# WS2812.net
KiCad netlist of a schematic drawn in Altium Designer
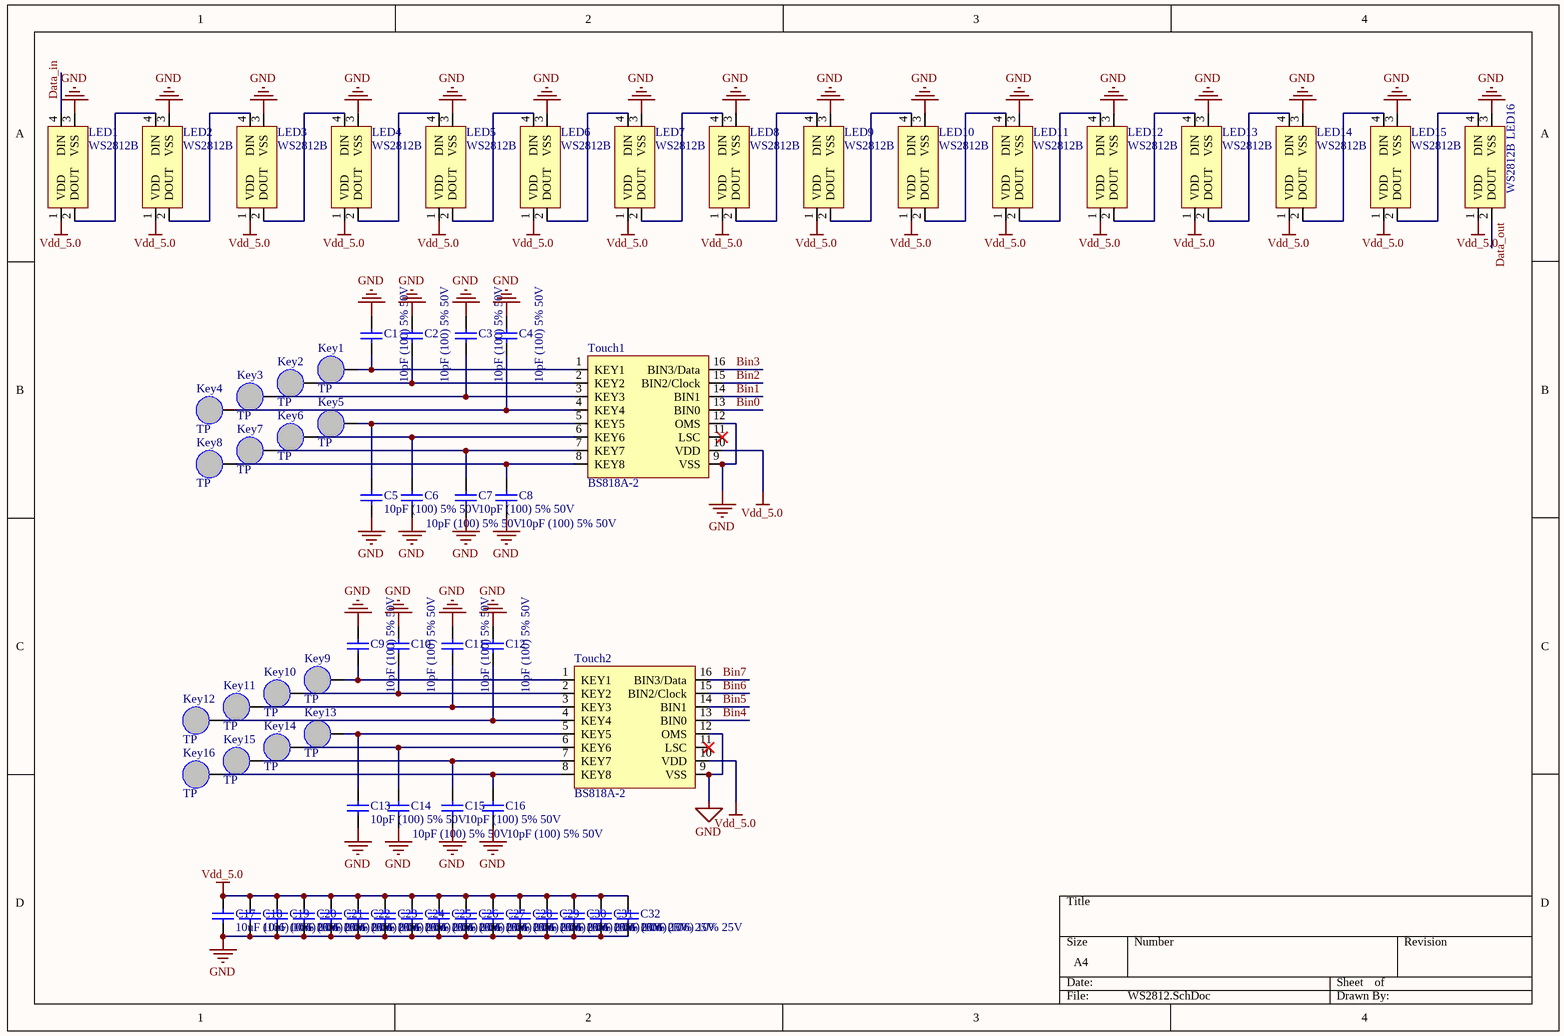
[diagram p0: WS2812.SchDoc]

(export (version "E")
  (design (tool "Eeschema 10.0.6"))
  (components
    (comp (ref "C1")
      (value "10pF (100) 5% 50V")
      (footprint "0603_C")
      (description "贴片电容")
      (libsource (lib "Miscellaneous Devices LC") (part "0603 10pF (100) 5% 50V"))
    )
    (comp (ref "C2")
      (value "10pF (100) 5% 50V")
      (footprint "0603_C")
      (description "贴片电容")
      (libsource (lib "Miscellaneous Devices LC") (part "0603 10pF (100) 5% 50V"))
    )
    (comp (ref "C3")
      (value "10pF (100) 5% 50V")
      (footprint "0603_C")
      (description "贴片电容")
      (libsource (lib "Miscellaneous Devices LC") (part "0603 10pF (100) 5% 50V"))
    )
    (comp (ref "C4")
      (value "10pF (100) 5% 50V")
      (footprint "0603_C")
      (description "贴片电容")
      (libsource (lib "Miscellaneous Devices LC") (part "0603 10pF (100) 5% 50V"))
    )
    (comp (ref "C5")
      (value "10pF (100) 5% 50V")
      (footprint "0603_C")
      (description "贴片电容")
      (libsource (lib "Miscellaneous Devices LC") (part "0603 10pF (100) 5% 50V"))
    )
    (comp (ref "C6")
      (value "10pF (100) 5% 50V")
      (footprint "0603_C")
      (description "贴片电容")
      (libsource (lib "Miscellaneous Devices LC") (part "0603 10pF (100) 5% 50V"))
    )
    (comp (ref "C7")
      (value "10pF (100) 5% 50V")
      (footprint "0603_C")
      (description "贴片电容")
      (libsource (lib "Miscellaneous Devices LC") (part "0603 10pF (100) 5% 50V"))
    )
    (comp (ref "C8")
      (value "10pF (100) 5% 50V")
      (footprint "0603_C")
      (description "贴片电容")
      (libsource (lib "Miscellaneous Devices LC") (part "0603 10pF (100) 5% 50V"))
    )
    (comp (ref "C9")
      (value "10pF (100) 5% 50V")
      (footprint "0603_C")
      (description "贴片电容")
      (libsource (lib "Miscellaneous Devices LC") (part "0603 10pF (100) 5% 50V"))
    )
    (comp (ref "C10")
      (value "10pF (100) 5% 50V")
      (footprint "0603_C")
      (description "贴片电容")
      (libsource (lib "Miscellaneous Devices LC") (part "0603 10pF (100) 5% 50V"))
    )
    (comp (ref "C11")
      (value "10pF (100) 5% 50V")
      (footprint "0603_C")
      (description "贴片电容")
      (libsource (lib "Miscellaneous Devices LC") (part "0603 10pF (100) 5% 50V"))
    )
    (comp (ref "C12")
      (value "10pF (100) 5% 50V")
      (footprint "0603_C")
      (description "贴片电容")
      (libsource (lib "Miscellaneous Devices LC") (part "0603 10pF (100) 5% 50V"))
    )
    (comp (ref "C13")
      (value "10pF (100) 5% 50V")
      (footprint "0603_C")
      (description "贴片电容")
      (libsource (lib "Miscellaneous Devices LC") (part "0603 10pF (100) 5% 50V"))
    )
    (comp (ref "C14")
      (value "10pF (100) 5% 50V")
      (footprint "0603_C")
      (description "贴片电容")
      (libsource (lib "Miscellaneous Devices LC") (part "0603 10pF (100) 5% 50V"))
    )
    (comp (ref "C15")
      (value "10pF (100) 5% 50V")
      (footprint "0603_C")
      (description "贴片电容")
      (libsource (lib "Miscellaneous Devices LC") (part "0603 10pF (100) 5% 50V"))
    )
    (comp (ref "C16")
      (value "10pF (100) 5% 50V")
      (footprint "0603_C")
      (description "贴片电容")
      (libsource (lib "Miscellaneous Devices LC") (part "0603 10pF (100) 5% 50V"))
    )
    (comp (ref "C17")
      (value "10uF (106) 10% 25V")
      (footprint "0805_C")
      (description "贴片电容")
      (libsource (lib "Miscellaneous Devices LC") (part "0805 10uF (106) 10% 25V"))
    )
    (comp (ref "C18")
      (value "10uF (106) 10% 25V")
      (footprint "0805_C")
      (description "贴片电容")
      (libsource (lib "Miscellaneous Devices LC") (part "0805 10uF (106) 10% 25V"))
    )
    (comp (ref "C19")
      (value "10uF (106) 10% 25V")
      (footprint "0805_C")
      (description "贴片电容")
      (libsource (lib "Miscellaneous Devices LC") (part "0805 10uF (106) 10% 25V"))
    )
    (comp (ref "C20")
      (value "10uF (106) 10% 25V")
      (footprint "0805_C")
      (description "贴片电容")
      (libsource (lib "Miscellaneous Devices LC") (part "0805 10uF (106) 10% 25V"))
    )
    (comp (ref "C21")
      (value "10uF (106) 10% 25V")
      (footprint "0805_C")
      (description "贴片电容")
      (libsource (lib "Miscellaneous Devices LC") (part "0805 10uF (106) 10% 25V"))
    )
    (comp (ref "C22")
      (value "10uF (106) 10% 25V")
      (footprint "0805_C")
      (description "贴片电容")
      (libsource (lib "Miscellaneous Devices LC") (part "0805 10uF (106) 10% 25V"))
    )
    (comp (ref "C23")
      (value "10uF (106) 10% 25V")
      (footprint "0805_C")
      (description "贴片电容")
      (libsource (lib "Miscellaneous Devices LC") (part "0805 10uF (106) 10% 25V"))
    )
    (comp (ref "C24")
      (value "10uF (106) 10% 25V")
      (footprint "0805_C")
      (description "贴片电容")
      (libsource (lib "Miscellaneous Devices LC") (part "0805 10uF (106) 10% 25V"))
    )
    (comp (ref "C25")
      (value "10uF (106) 10% 25V")
      (footprint "0805_C")
      (description "贴片电容")
      (libsource (lib "Miscellaneous Devices LC") (part "0805 10uF (106) 10% 25V"))
    )
    (comp (ref "C26")
      (value "10uF (106) 10% 25V")
      (footprint "0805_C")
      (description "贴片电容")
      (libsource (lib "Miscellaneous Devices LC") (part "0805 10uF (106) 10% 25V"))
    )
    (comp (ref "C27")
      (value "10uF (106) 10% 25V")
      (footprint "0805_C")
      (description "贴片电容")
      (libsource (lib "Miscellaneous Devices LC") (part "0805 10uF (106) 10% 25V"))
    )
    (comp (ref "C28")
      (value "10uF (106) 10% 25V")
      (footprint "0805_C")
      (description "贴片电容")
      (libsource (lib "Miscellaneous Devices LC") (part "0805 10uF (106) 10% 25V"))
    )
    (comp (ref "C29")
      (value "10uF (106) 10% 25V")
      (footprint "0805_C")
      (description "贴片电容")
      (libsource (lib "Miscellaneous Devices LC") (part "0805 10uF (106) 10% 25V"))
    )
    (comp (ref "C30")
      (value "10uF (106) 10% 25V")
      (footprint "0805_C")
      (description "贴片电容")
      (libsource (lib "Miscellaneous Devices LC") (part "0805 10uF (106) 10% 25V"))
    )
    (comp (ref "C31")
      (value "10uF (106) 10% 25V")
      (footprint "0805_C")
      (description "贴片电容")
      (libsource (lib "Miscellaneous Devices LC") (part "0805 10uF (106) 10% 25V"))
    )
    (comp (ref "C32")
      (value "10uF (106) 10% 25V")
      (footprint "0805_C")
      (description "贴片电容")
      (libsource (lib "Miscellaneous Devices LC") (part "0805 10uF (106) 10% 25V"))
    )
    (comp (ref "Key1") (value "TP") (footprint "Spring_touch") (libsource (lib "mylib") (part "TP")))
    (comp (ref "Key2") (value "TP") (footprint "Spring_touch") (libsource (lib "mylib") (part "TP")))
    (comp (ref "Key3") (value "TP") (footprint "Spring_touch") (libsource (lib "mylib") (part "TP")))
    (comp (ref "Key4") (value "TP") (footprint "Spring_touch") (libsource (lib "mylib") (part "TP")))
    (comp (ref "Key5") (value "TP") (footprint "Spring_touch") (libsource (lib "mylib") (part "TP")))
    (comp (ref "Key6") (value "TP") (footprint "Spring_touch") (libsource (lib "mylib") (part "TP")))
    (comp (ref "Key7") (value "TP") (footprint "Spring_touch") (libsource (lib "mylib") (part "TP")))
    (comp (ref "Key8") (value "TP") (footprint "Spring_touch") (libsource (lib "mylib") (part "TP")))
    (comp (ref "Key9") (value "TP") (footprint "Spring_touch") (libsource (lib "mylib") (part "TP")))
    (comp (ref "Key10") (value "TP") (footprint "Spring_touch") (libsource (lib "mylib") (part "TP")))
    (comp (ref "Key11") (value "TP") (footprint "Spring_touch") (libsource (lib "mylib") (part "TP")))
    (comp (ref "Key12") (value "TP") (footprint "Spring_touch") (libsource (lib "mylib") (part "TP")))
    (comp (ref "Key13") (value "TP") (footprint "Spring_touch") (libsource (lib "mylib") (part "TP")))
    (comp (ref "Key14") (value "TP") (footprint "Spring_touch") (libsource (lib "mylib") (part "TP")))
    (comp (ref "Key15") (value "TP") (footprint "Spring_touch") (libsource (lib "mylib") (part "TP")))
    (comp (ref "Key16") (value "TP") (footprint "Spring_touch") (libsource (lib "mylib") (part "TP")))
    (comp (ref "LED1") (value "WS2812B") (footprint "WS2812") (libsource (lib "mylib") (part "WS2812B")))
    (comp (ref "LED2") (value "WS2812B") (footprint "WS2812") (libsource (lib "mylib") (part "WS2812B")))
    (comp (ref "LED3") (value "WS2812B") (footprint "WS2812") (libsource (lib "mylib") (part "WS2812B")))
    (comp (ref "LED4") (value "WS2812B") (footprint "WS2812") (libsource (lib "mylib") (part "WS2812B")))
    (comp (ref "LED5") (value "WS2812B") (footprint "WS2812") (libsource (lib "mylib") (part "WS2812B")))
    (comp (ref "LED6") (value "WS2812B") (footprint "WS2812") (libsource (lib "mylib") (part "WS2812B")))
    (comp (ref "LED7") (value "WS2812B") (footprint "WS2812") (libsource (lib "mylib") (part "WS2812B")))
    (comp (ref "LED8") (value "WS2812B") (footprint "WS2812") (libsource (lib "mylib") (part "WS2812B")))
    (comp (ref "LED9") (value "WS2812B") (footprint "WS2812") (libsource (lib "mylib") (part "WS2812B")))
    (comp (ref "LED10") (value "WS2812B") (footprint "WS2812") (libsource (lib "mylib") (part "WS2812B")))
    (comp (ref "LED11") (value "WS2812B") (footprint "WS2812") (libsource (lib "mylib") (part "WS2812B")))
    (comp (ref "LED12") (value "WS2812B") (footprint "WS2812") (libsource (lib "mylib") (part "WS2812B")))
    (comp (ref "LED13") (value "WS2812B") (footprint "WS2812") (libsource (lib "mylib") (part "WS2812B")))
    (comp (ref "LED14") (value "WS2812B") (footprint "WS2812") (libsource (lib "mylib") (part "WS2812B")))
    (comp (ref "LED15") (value "WS2812B") (footprint "WS2812") (libsource (lib "mylib") (part "WS2812B")))
    (comp (ref "LED16") (value "WS2812B") (footprint "WS2812") (libsource (lib "mylib") (part "WS2812B")))
    (comp (ref "Touch1") (value "BS818A-2") (footprint "SO-16_N") (libsource (lib "mylib") (part "BS818A-2")))
    (comp (ref "Touch2") (value "BS818A-2") (footprint "SO-16_N") (libsource (lib "mylib") (part "BS818A-2")))
  )
  (nets
    (net (code "1") (name "/Bin0") (class "Default")
      (node (ref "Touch1") (pin "13") (pinfunction "BIN0_13") (pintype "passive"))
    )
    (net (code "2") (name "/Bin1") (class "Default")
      (node (ref "Touch1") (pin "14") (pinfunction "BIN1_14") (pintype "passive"))
    )
    (net (code "3") (name "/Bin2") (class "Default")
      (node (ref "Touch1") (pin "15") (pinfunction "BIN2/Clock_15") (pintype "passive"))
    )
    (net (code "4") (name "/Bin3") (class "Default")
      (node (ref "Touch1") (pin "16") (pinfunction "BIN3/Data_16") (pintype "passive"))
    )
    (net (code "5") (name "/Bin4") (class "Default")
      (node (ref "Touch2") (pin "13") (pinfunction "BIN0_13") (pintype "passive"))
    )
    (net (code "6") (name "/Bin5") (class "Default")
      (node (ref "Touch2") (pin "14") (pinfunction "BIN1_14") (pintype "passive"))
    )
    (net (code "7") (name "/Bin6") (class "Default")
      (node (ref "Touch2") (pin "15") (pinfunction "BIN2/Clock_15") (pintype "passive"))
    )
    (net (code "8") (name "/Bin7") (class "Default")
      (node (ref "Touch2") (pin "16") (pinfunction "BIN3/Data_16") (pintype "passive"))
    )
    (net (code "9") (name "/Data_in") (class "Default")
      (node (ref "LED1") (pin "4") (pinfunction "DIN_4") (pintype "passive"))
    )
    (net (code "10") (name "/Data_out") (class "Default")
      (node (ref "LED16") (pin "2") (pinfunction "DOUT_2") (pintype "passive"))
    )
    (net (code "11") (name "GND") (class "Default")
      (node (ref "C1") (pin "2") (pinfunction "2_2") (pintype "passive"))
      (node (ref "C10") (pin "2") (pinfunction "2_2") (pintype "passive"))
      (node (ref "C11") (pin "2") (pinfunction "2_2") (pintype "passive"))
      (node (ref "C12") (pin "2") (pinfunction "2_2") (pintype "passive"))
      (node (ref "C13") (pin "2") (pinfunction "2_2") (pintype "passive"))
      (node (ref "C14") (pin "2") (pinfunction "2_2") (pintype "passive"))
      (node (ref "C15") (pin "2") (pinfunction "2_2") (pintype "passive"))
      (node (ref "C16") (pin "2") (pinfunction "2_2") (pintype "passive"))
      (node (ref "C17") (pin "1") (pinfunction "1_1") (pintype "passive"))
      (node (ref "C18") (pin "1") (pinfunction "1_1") (pintype "passive"))
      (node (ref "C19") (pin "1") (pinfunction "1_1") (pintype "passive"))
      (node (ref "C2") (pin "2") (pinfunction "2_2") (pintype "passive"))
      (node (ref "C20") (pin "1") (pinfunction "1_1") (pintype "passive"))
      (node (ref "C21") (pin "1") (pinfunction "1_1") (pintype "passive"))
      (node (ref "C22") (pin "1") (pinfunction "1_1") (pintype "passive"))
      (node (ref "C23") (pin "1") (pinfunction "1_1") (pintype "passive"))
      (node (ref "C24") (pin "1") (pinfunction "1_1") (pintype "passive"))
      (node (ref "C25") (pin "1") (pinfunction "1_1") (pintype "passive"))
      (node (ref "C26") (pin "1") (pinfunction "1_1") (pintype "passive"))
      (node (ref "C27") (pin "1") (pinfunction "1_1") (pintype "passive"))
      (node (ref "C28") (pin "1") (pinfunction "1_1") (pintype "passive"))
      (node (ref "C29") (pin "1") (pinfunction "1_1") (pintype "passive"))
      (node (ref "C3") (pin "2") (pinfunction "2_2") (pintype "passive"))
      (node (ref "C30") (pin "1") (pinfunction "1_1") (pintype "passive"))
      (node (ref "C31") (pin "1") (pinfunction "1_1") (pintype "passive"))
      (node (ref "C32") (pin "1") (pinfunction "1_1") (pintype "passive"))
      (node (ref "C4") (pin "2") (pinfunction "2_2") (pintype "passive"))
      (node (ref "C5") (pin "2") (pinfunction "2_2") (pintype "passive"))
      (node (ref "C6") (pin "2") (pinfunction "2_2") (pintype "passive"))
      (node (ref "C7") (pin "2") (pinfunction "2_2") (pintype "passive"))
      (node (ref "C8") (pin "2") (pinfunction "2_2") (pintype "passive"))
      (node (ref "C9") (pin "2") (pinfunction "2_2") (pintype "passive"))
      (node (ref "LED1") (pin "3") (pinfunction "VSS_3") (pintype "passive"))
      (node (ref "LED10") (pin "3") (pinfunction "VSS_3") (pintype "passive"))
      (node (ref "LED11") (pin "3") (pinfunction "VSS_3") (pintype "passive"))
      (node (ref "LED12") (pin "3") (pinfunction "VSS_3") (pintype "passive"))
      (node (ref "LED13") (pin "3") (pinfunction "VSS_3") (pintype "passive"))
      (node (ref "LED14") (pin "3") (pinfunction "VSS_3") (pintype "passive"))
      (node (ref "LED15") (pin "3") (pinfunction "VSS_3") (pintype "passive"))
      (node (ref "LED16") (pin "3") (pinfunction "VSS_3") (pintype "passive"))
      (node (ref "LED2") (pin "3") (pinfunction "VSS_3") (pintype "passive"))
      (node (ref "LED3") (pin "3") (pinfunction "VSS_3") (pintype "passive"))
      (node (ref "LED4") (pin "3") (pinfunction "VSS_3") (pintype "passive"))
      (node (ref "LED5") (pin "3") (pinfunction "VSS_3") (pintype "passive"))
      (node (ref "LED6") (pin "3") (pinfunction "VSS_3") (pintype "passive"))
      (node (ref "LED7") (pin "3") (pinfunction "VSS_3") (pintype "passive"))
      (node (ref "LED8") (pin "3") (pinfunction "VSS_3") (pintype "passive"))
      (node (ref "LED9") (pin "3") (pinfunction "VSS_3") (pintype "passive"))
      (node (ref "Touch1") (pin "12") (pinfunction "OMS_12") (pintype "passive"))
      (node (ref "Touch1") (pin "9") (pinfunction "VSS_9") (pintype "passive"))
      (node (ref "Touch2") (pin "12") (pinfunction "OMS_12") (pintype "passive"))
      (node (ref "Touch2") (pin "9") (pinfunction "VSS_9") (pintype "passive"))
    )
    (net (code "12") (name "Net-(LED1-DOUT)") (class "Default")
      (node (ref "LED1") (pin "2") (pinfunction "DOUT_2") (pintype "passive"))
      (node (ref "LED2") (pin "4") (pinfunction "DIN_4") (pintype "passive"))
    )
    (net (code "13") (name "Net-(LED2-DOUT)") (class "Default")
      (node (ref "LED2") (pin "2") (pinfunction "DOUT_2") (pintype "passive"))
      (node (ref "LED3") (pin "4") (pinfunction "DIN_4") (pintype "passive"))
    )
    (net (code "14") (name "Net-(LED3-DOUT)") (class "Default")
      (node (ref "LED3") (pin "2") (pinfunction "DOUT_2") (pintype "passive"))
      (node (ref "LED4") (pin "4") (pinfunction "DIN_4") (pintype "passive"))
    )
    (net (code "15") (name "Net-(LED4-DOUT)") (class "Default")
      (node (ref "LED4") (pin "2") (pinfunction "DOUT_2") (pintype "passive"))
      (node (ref "LED5") (pin "4") (pinfunction "DIN_4") (pintype "passive"))
    )
    (net (code "16") (name "Net-(LED5-DOUT)") (class "Default")
      (node (ref "LED5") (pin "2") (pinfunction "DOUT_2") (pintype "passive"))
      (node (ref "LED6") (pin "4") (pinfunction "DIN_4") (pintype "passive"))
    )
    (net (code "17") (name "Net-(LED6-DOUT)") (class "Default")
      (node (ref "LED6") (pin "2") (pinfunction "DOUT_2") (pintype "passive"))
      (node (ref "LED7") (pin "4") (pinfunction "DIN_4") (pintype "passive"))
    )
    (net (code "18") (name "Net-(LED7-DOUT)") (class "Default")
      (node (ref "LED7") (pin "2") (pinfunction "DOUT_2") (pintype "passive"))
      (node (ref "LED8") (pin "4") (pinfunction "DIN_4") (pintype "passive"))
    )
    (net (code "19") (name "Net-(LED8-DOUT)") (class "Default")
      (node (ref "LED8") (pin "2") (pinfunction "DOUT_2") (pintype "passive"))
      (node (ref "LED9") (pin "4") (pinfunction "DIN_4") (pintype "passive"))
    )
    (net (code "20") (name "Net-(LED10-DIN)") (class "Default")
      (node (ref "LED10") (pin "4") (pinfunction "DIN_4") (pintype "passive"))
      (node (ref "LED9") (pin "2") (pinfunction "DOUT_2") (pintype "passive"))
    )
    (net (code "21") (name "Net-(LED10-DOUT)") (class "Default")
      (node (ref "LED10") (pin "2") (pinfunction "DOUT_2") (pintype "passive"))
      (node (ref "LED11") (pin "4") (pinfunction "DIN_4") (pintype "passive"))
    )
    (net (code "22") (name "Net-(LED11-DOUT)") (class "Default")
      (node (ref "LED11") (pin "2") (pinfunction "DOUT_2") (pintype "passive"))
      (node (ref "LED12") (pin "4") (pinfunction "DIN_4") (pintype "passive"))
    )
    (net (code "23") (name "Net-(LED12-DOUT)") (class "Default")
      (node (ref "LED12") (pin "2") (pinfunction "DOUT_2") (pintype "passive"))
      (node (ref "LED13") (pin "4") (pinfunction "DIN_4") (pintype "passive"))
    )
    (net (code "24") (name "Net-(LED13-DOUT)") (class "Default")
      (node (ref "LED13") (pin "2") (pinfunction "DOUT_2") (pintype "passive"))
      (node (ref "LED14") (pin "4") (pinfunction "DIN_4") (pintype "passive"))
    )
    (net (code "25") (name "Net-(LED14-DOUT)") (class "Default")
      (node (ref "LED14") (pin "2") (pinfunction "DOUT_2") (pintype "passive"))
      (node (ref "LED15") (pin "4") (pinfunction "DIN_4") (pintype "passive"))
    )
    (net (code "26") (name "Net-(LED15-DOUT)") (class "Default")
      (node (ref "LED15") (pin "2") (pinfunction "DOUT_2") (pintype "passive"))
      (node (ref "LED16") (pin "4") (pinfunction "DIN_4") (pintype "passive"))
    )
    (net (code "27") (name "Net-(Touch1-KEY1)") (class "Default")
      (node (ref "C1") (pin "1") (pinfunction "1_1") (pintype "passive"))
      (node (ref "Key1") (pin "1") (pinfunction "1_1") (pintype "passive"))
      (node (ref "Touch1") (pin "1") (pinfunction "KEY1_1") (pintype "passive"))
    )
    (net (code "28") (name "Net-(Touch1-KEY2)") (class "Default")
      (node (ref "C2") (pin "1") (pinfunction "1_1") (pintype "passive"))
      (node (ref "Key2") (pin "1") (pinfunction "1_1") (pintype "passive"))
      (node (ref "Touch1") (pin "2") (pinfunction "KEY2_2") (pintype "passive"))
    )
    (net (code "29") (name "Net-(Touch1-KEY3)") (class "Default")
      (node (ref "C3") (pin "1") (pinfunction "1_1") (pintype "passive"))
      (node (ref "Key3") (pin "1") (pinfunction "1_1") (pintype "passive"))
      (node (ref "Touch1") (pin "3") (pinfunction "KEY3_3") (pintype "passive"))
    )
    (net (code "30") (name "Net-(Touch1-KEY4)") (class "Default")
      (node (ref "C4") (pin "1") (pinfunction "1_1") (pintype "passive"))
      (node (ref "Key4") (pin "1") (pinfunction "1_1") (pintype "passive"))
      (node (ref "Touch1") (pin "4") (pinfunction "KEY4_4") (pintype "passive"))
    )
    (net (code "31") (name "Net-(Touch1-KEY5)") (class "Default")
      (node (ref "C5") (pin "1") (pinfunction "1_1") (pintype "passive"))
      (node (ref "Key5") (pin "1") (pinfunction "1_1") (pintype "passive"))
      (node (ref "Touch1") (pin "5") (pinfunction "KEY5_5") (pintype "passive"))
    )
    (net (code "32") (name "Net-(Touch1-KEY6)") (class "Default")
      (node (ref "C6") (pin "1") (pinfunction "1_1") (pintype "passive"))
      (node (ref "Key6") (pin "1") (pinfunction "1_1") (pintype "passive"))
      (node (ref "Touch1") (pin "6") (pinfunction "KEY6_6") (pintype "passive"))
    )
    (net (code "33") (name "Net-(Touch1-KEY7)") (class "Default")
      (node (ref "C7") (pin "1") (pinfunction "1_1") (pintype "passive"))
      (node (ref "Key7") (pin "1") (pinfunction "1_1") (pintype "passive"))
      (node (ref "Touch1") (pin "7") (pinfunction "KEY7_7") (pintype "passive"))
    )
    (net (code "34") (name "Net-(Touch1-KEY8)") (class "Default")
      (node (ref "C8") (pin "1") (pinfunction "1_1") (pintype "passive"))
      (node (ref "Key8") (pin "1") (pinfunction "1_1") (pintype "passive"))
      (node (ref "Touch1") (pin "8") (pinfunction "KEY8_8") (pintype "passive"))
    )
    (net (code "35") (name "Net-(Touch2-KEY1)") (class "Default")
      (node (ref "C9") (pin "1") (pinfunction "1_1") (pintype "passive"))
      (node (ref "Key9") (pin "1") (pinfunction "1_1") (pintype "passive"))
      (node (ref "Touch2") (pin "1") (pinfunction "KEY1_1") (pintype "passive"))
    )
    (net (code "36") (name "Net-(Touch2-KEY2)") (class "Default")
      (node (ref "C10") (pin "1") (pinfunction "1_1") (pintype "passive"))
      (node (ref "Key10") (pin "1") (pinfunction "1_1") (pintype "passive"))
      (node (ref "Touch2") (pin "2") (pinfunction "KEY2_2") (pintype "passive"))
    )
    (net (code "37") (name "Net-(Touch2-KEY3)") (class "Default")
      (node (ref "C11") (pin "1") (pinfunction "1_1") (pintype "passive"))
      (node (ref "Key11") (pin "1") (pinfunction "1_1") (pintype "passive"))
      (node (ref "Touch2") (pin "3") (pinfunction "KEY3_3") (pintype "passive"))
    )
    (net (code "38") (name "Net-(Touch2-KEY4)") (class "Default")
      (node (ref "C12") (pin "1") (pinfunction "1_1") (pintype "passive"))
      (node (ref "Key12") (pin "1") (pinfunction "1_1") (pintype "passive"))
      (node (ref "Touch2") (pin "4") (pinfunction "KEY4_4") (pintype "passive"))
    )
    (net (code "39") (name "Net-(Touch2-KEY5)") (class "Default")
      (node (ref "C13") (pin "1") (pinfunction "1_1") (pintype "passive"))
      (node (ref "Key13") (pin "1") (pinfunction "1_1") (pintype "passive"))
      (node (ref "Touch2") (pin "5") (pinfunction "KEY5_5") (pintype "passive"))
    )
    (net (code "40") (name "Net-(Touch2-KEY6)") (class "Default")
      (node (ref "C14") (pin "1") (pinfunction "1_1") (pintype "passive"))
      (node (ref "Key14") (pin "1") (pinfunction "1_1") (pintype "passive"))
      (node (ref "Touch2") (pin "6") (pinfunction "KEY6_6") (pintype "passive"))
    )
    (net (code "41") (name "Net-(Touch2-KEY7)") (class "Default")
      (node (ref "C15") (pin "1") (pinfunction "1_1") (pintype "passive"))
      (node (ref "Key15") (pin "1") (pinfunction "1_1") (pintype "passive"))
      (node (ref "Touch2") (pin "7") (pinfunction "KEY7_7") (pintype "passive"))
    )
    (net (code "42") (name "Net-(Touch2-KEY8)") (class "Default")
      (node (ref "C16") (pin "1") (pinfunction "1_1") (pintype "passive"))
      (node (ref "Key16") (pin "1") (pinfunction "1_1") (pintype "passive"))
      (node (ref "Touch2") (pin "8") (pinfunction "KEY8_8") (pintype "passive"))
    )
    (net (code "43") (name "Vdd_5.0") (class "Default")
      (node (ref "C17") (pin "2") (pinfunction "2_2") (pintype "passive"))
      (node (ref "C18") (pin "2") (pinfunction "2_2") (pintype "passive"))
      (node (ref "C19") (pin "2") (pinfunction "2_2") (pintype "passive"))
      (node (ref "C20") (pin "2") (pinfunction "2_2") (pintype "passive"))
      (node (ref "C21") (pin "2") (pinfunction "2_2") (pintype "passive"))
      (node (ref "C22") (pin "2") (pinfunction "2_2") (pintype "passive"))
      (node (ref "C23") (pin "2") (pinfunction "2_2") (pintype "passive"))
      (node (ref "C24") (pin "2") (pinfunction "2_2") (pintype "passive"))
      (node (ref "C25") (pin "2") (pinfunction "2_2") (pintype "passive"))
      (node (ref "C26") (pin "2") (pinfunction "2_2") (pintype "passive"))
      (node (ref "C27") (pin "2") (pinfunction "2_2") (pintype "passive"))
      (node (ref "C28") (pin "2") (pinfunction "2_2") (pintype "passive"))
      (node (ref "C29") (pin "2") (pinfunction "2_2") (pintype "passive"))
      (node (ref "C30") (pin "2") (pinfunction "2_2") (pintype "passive"))
      (node (ref "C31") (pin "2") (pinfunction "2_2") (pintype "passive"))
      (node (ref "C32") (pin "2") (pinfunction "2_2") (pintype "passive"))
      (node (ref "LED1") (pin "1") (pinfunction "VDD_1") (pintype "passive"))
      (node (ref "LED10") (pin "1") (pinfunction "VDD_1") (pintype "passive"))
      (node (ref "LED11") (pin "1") (pinfunction "VDD_1") (pintype "passive"))
      (node (ref "LED12") (pin "1") (pinfunction "VDD_1") (pintype "passive"))
      (node (ref "LED13") (pin "1") (pinfunction "VDD_1") (pintype "passive"))
      (node (ref "LED14") (pin "1") (pinfunction "VDD_1") (pintype "passive"))
      (node (ref "LED15") (pin "1") (pinfunction "VDD_1") (pintype "passive"))
      (node (ref "LED16") (pin "1") (pinfunction "VDD_1") (pintype "passive"))
      (node (ref "LED2") (pin "1") (pinfunction "VDD_1") (pintype "passive"))
      (node (ref "LED3") (pin "1") (pinfunction "VDD_1") (pintype "passive"))
      (node (ref "LED4") (pin "1") (pinfunction "VDD_1") (pintype "passive"))
      (node (ref "LED5") (pin "1") (pinfunction "VDD_1") (pintype "passive"))
      (node (ref "LED6") (pin "1") (pinfunction "VDD_1") (pintype "passive"))
      (node (ref "LED7") (pin "1") (pinfunction "VDD_1") (pintype "passive"))
      (node (ref "LED8") (pin "1") (pinfunction "VDD_1") (pintype "passive"))
      (node (ref "LED9") (pin "1") (pinfunction "VDD_1") (pintype "passive"))
      (node (ref "Touch1") (pin "10") (pinfunction "VDD_10") (pintype "passive"))
      (node (ref "Touch2") (pin "10") (pinfunction "VDD_10") (pintype "passive"))
    )
    (net (code "44") (name "unconnected-(Touch1-LSC-Pad11)") (class "Default")
      (node (ref "Touch1") (pin "11") (pinfunction "LSC_11") (pintype "passive+no_connect"))
    )
    (net (code "45") (name "unconnected-(Touch2-LSC-Pad11)") (class "Default")
      (node (ref "Touch2") (pin "11") (pinfunction "LSC_11") (pintype "passive+no_connect"))
    )
  )
)
